# W51FXXXXS16_EVB_NONOFFICIAL_2026-06-30.net
KiCad netlist of a schematic drawn in EasyEDA Pro
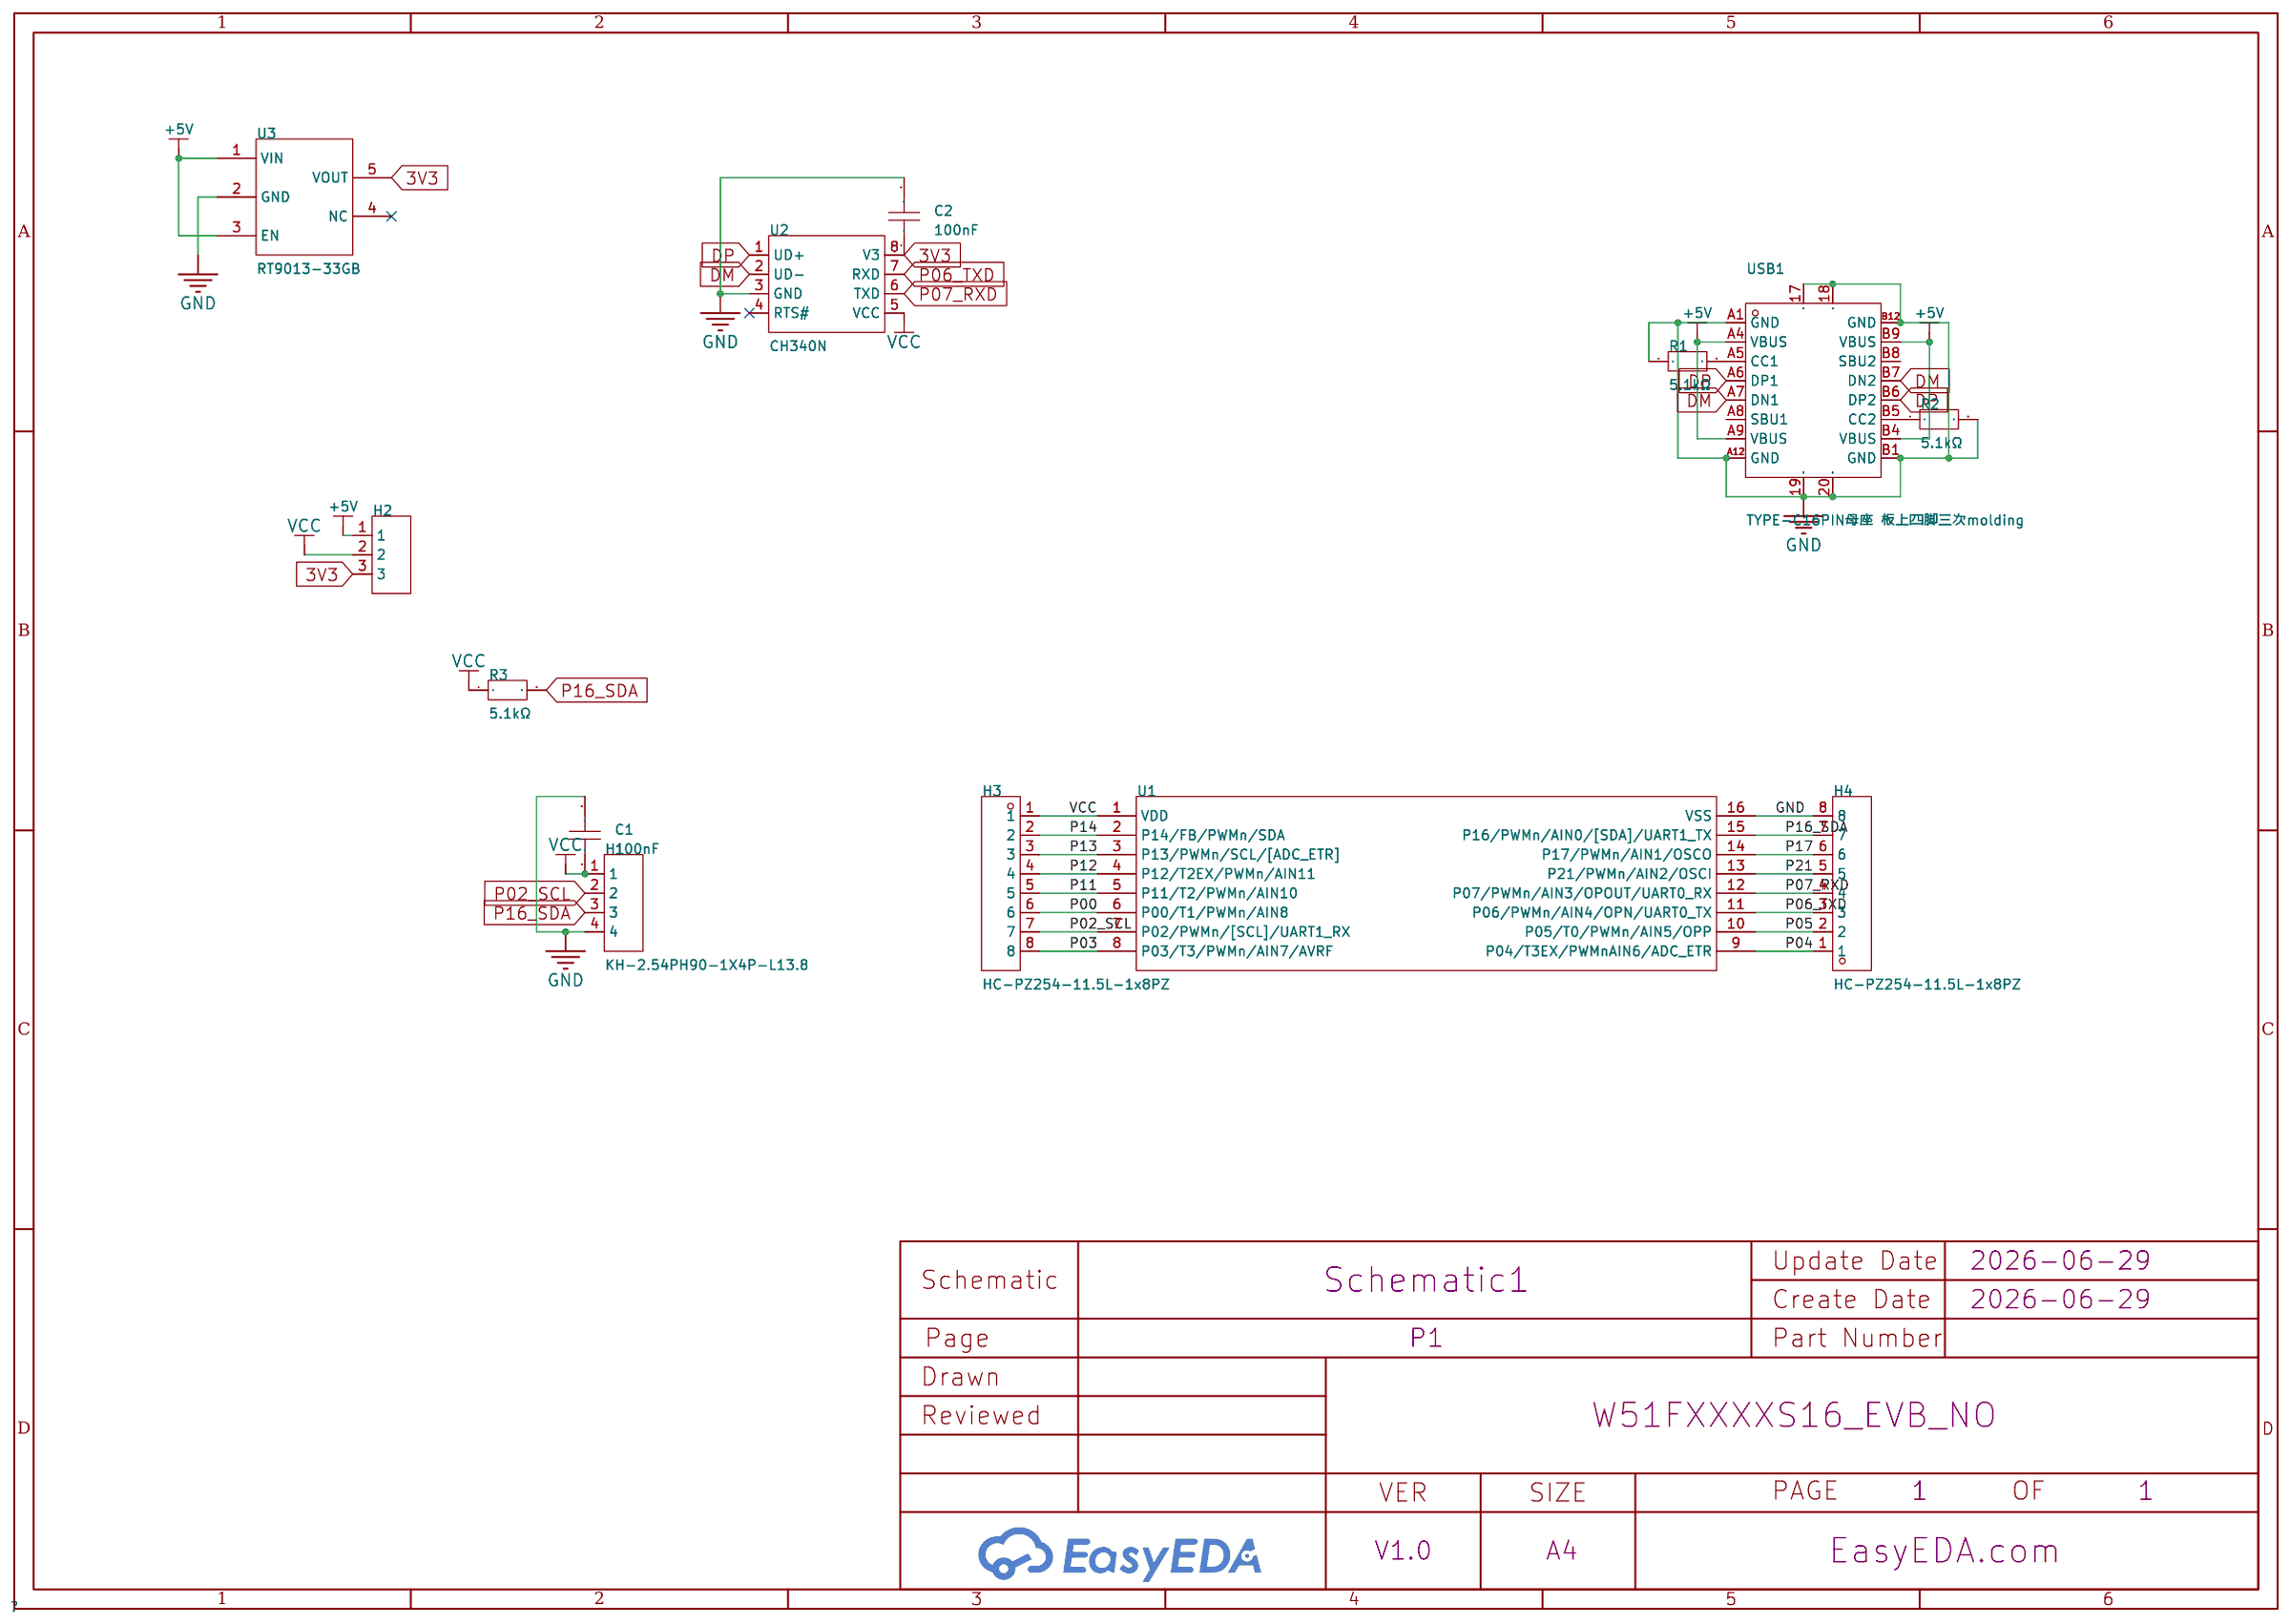
[diagram p0: schematic sheet]

(export (version "E")
  (design (tool "Eeschema 10.0.6"))
  (components
    (comp (ref "C1")
      (value "100nF")
      (footprint "easyedapro:C1206")
      (description "Capacitance:100nF Tolerance:±10% Tolerance:±10% Voltage Rating:200V Temperature Coefficient:X7R")
      (fields
        (field (name "Manufacturer Part") "VJ1206Y104KLCAJ32")
        (field (name "Manufacturer") "VISHAY(威世)")
      )
      (libsource (lib "easyedapro") (part "VJ1206Y104KLCAJ32"))
    )
    (comp (ref "C2")
      (value "100nF")
      (footprint "easyedapro:C1206")
      (description "Capacitance:100nF Tolerance:±10% Tolerance:±10% Voltage Rating:200V Temperature Coefficient:X7R")
      (fields
        (field (name "Manufacturer Part") "VJ1206Y104KLCAJ32")
        (field (name "Manufacturer") "VISHAY(威世)")
      )
      (libsource (lib "easyedapro") (part "VJ1206Y104KLCAJ32"))
    )
    (comp (ref "H1")
      (value "KH-2.54PH90-1X4P-L13.8")
      (footprint "easyedapro:HDR-TH_4P-P2.54-H-M-W10.4-N")
      (fields (field (name "Manufacturer") "kinghelm(金航标)"))
      (libsource (lib "easyedapro") (part "KH-2.54PH90-1X4P-L13.8"))
    )
    (comp (ref "H2")
      (value "~")
      (footprint "easyedapro:HDR-TH_3P-P2.54-V-M")
      (libsource (lib "easyedapro") (part "PZ254V-11-03P_C2937625"))
    )
    (comp (ref "H3")
      (value "HC-PZ254-11.5L-1x8PZ")
      (footprint "easyedapro:HDR-TH_8P-P2.54-V-M")
      (fields (field (name "Manufacturer") "HC(虹成电子)"))
      (libsource (lib "easyedapro") (part "HC-PZ254-11.5L-1X8PZ"))
    )
    (comp (ref "H4")
      (value "HC-PZ254-11.5L-1x8PZ")
      (footprint "easyedapro:HDR-TH_8P-P2.54-V-M")
      (fields (field (name "Manufacturer") "HC(虹成电子)"))
      (libsource (lib "easyedapro") (part "HC-PZ254-11.5L-1X8PZ"))
    )
    (comp (ref "R1")
      (value "5.1kΩ")
      (footprint "easyedapro:R1206")
      (fields
        (field (name "Manufacturer Part") "CQ06W4F5101T5E")
        (field (name "Manufacturer") "UNI-ROYAL(厚声)")
      )
      (libsource (lib "easyedapro") (part "CQ06W4F5101T5E"))
    )
    (comp (ref "R2")
      (value "5.1kΩ")
      (footprint "easyedapro:R1206")
      (fields
        (field (name "Manufacturer Part") "CQ06W4F5101T5E")
        (field (name "Manufacturer") "UNI-ROYAL(厚声)")
      )
      (libsource (lib "easyedapro") (part "CQ06W4F5101T5E"))
    )
    (comp (ref "R3")
      (value "5.1kΩ")
      (footprint "easyedapro:R1206")
      (fields
        (field (name "Manufacturer Part") "CQ06W4F5101T5E")
        (field (name "Manufacturer") "UNI-ROYAL(厚声)")
      )
      (libsource (lib "easyedapro") (part "CQ06W4F5101T5E"))
    )
    (comp (ref "U1")
      (value "~")
      (description "Low cost 1T 8051 MCU")
      (libsource (lib "easyedapro") (part "W51F6240S16"))
    )
    (comp (ref "U2")
      (value "CH340N")
      (footprint "easyedapro:SOP-8_L4.9-W3.9-P1.27-LS6.0-BL")
      (fields (field (name "Manufacturer") "WCH(南京沁恒)"))
      (libsource (lib "easyedapro") (part "CH340N_C2977777"))
    )
    (comp (ref "U3")
      (value "RT9013-33GB")
      (footprint "easyedapro:SOT-23-5_L3.0-W1.7-P0.95-LS2.8-BL")
      (fields (field (name "Manufacturer") "RICHTEK(立锜)"))
      (libsource (lib "easyedapro") (part "RT9013-33GB"))
    )
    (comp (ref "USB1")
      (value "TYPE-C16PIN母座 板上四脚三次molding")
      (footprint "easyedapro:USB-SMD_TYPE-C16PIN")
      (libsource (lib "easyedapro") (part "TYPE-C16PIN母座 板上四脚三次MOLDING"))
    )
  )
  (nets
    (net (code "1") (name "+5V") (class "Default")
      (node (ref "H2") (pin "1") (pinfunction "1_1") (pintype "unspecified"))
      (node (ref "U3") (pin "1") (pinfunction "VIN_1") (pintype "unspecified"))
      (node (ref "U3") (pin "3") (pinfunction "EN_3") (pintype "unspecified"))
      (node (ref "USB1") (pin "A4") (pinfunction "VBUS_A4") (pintype "input"))
      (node (ref "USB1") (pin "A9") (pinfunction "VBUS_A9") (pintype "input"))
      (node (ref "USB1") (pin "B4") (pinfunction "VBUS_B4") (pintype "input"))
      (node (ref "USB1") (pin "B9") (pinfunction "VBUS_B9") (pintype "input"))
    )
    (net (code "2") (name "/P00") (class "Default")
      (node (ref "H3") (pin "6") (pinfunction "6_6") (pintype "unspecified"))
      (node (ref "U1") (pin "6") (pinfunction "P00/T1/PWMn/AIN8_6") (pintype "input"))
    )
    (net (code "3") (name "/P03") (class "Default")
      (node (ref "H3") (pin "8") (pinfunction "8_8") (pintype "unspecified"))
      (node (ref "U1") (pin "8") (pinfunction "P03/T3/PWMn/AIN7/AVRF_8") (pintype "input"))
    )
    (net (code "4") (name "/P04") (class "Default")
      (node (ref "H4") (pin "1") (pinfunction "1_1") (pintype "unspecified"))
      (node (ref "U1") (pin "9") (pinfunction "P04/T3EX/PWMnAIN6/ADC_ETR_9") (pintype "input"))
    )
    (net (code "5") (name "/P05") (class "Default")
      (node (ref "H4") (pin "2") (pinfunction "2_2") (pintype "unspecified"))
      (node (ref "U1") (pin "10") (pinfunction "P05/T0/PWMn/AIN5/OPP_10") (pintype "input"))
    )
    (net (code "6") (name "/P11") (class "Default")
      (node (ref "H3") (pin "5") (pinfunction "5_5") (pintype "unspecified"))
      (node (ref "U1") (pin "5") (pinfunction "P11/T2/PWMn/AIN10_5") (pintype "input"))
    )
    (net (code "7") (name "/P12") (class "Default")
      (node (ref "H3") (pin "4") (pinfunction "4_4") (pintype "unspecified"))
      (node (ref "U1") (pin "4") (pinfunction "P12/T2EX/PWMn/AIN11_4") (pintype "input"))
    )
    (net (code "8") (name "/P13") (class "Default")
      (node (ref "H3") (pin "3") (pinfunction "3_3") (pintype "unspecified"))
      (node (ref "U1") (pin "3") (pinfunction "P13/PWMn/SCL/[ADC_ETR]_3") (pintype "input"))
    )
    (net (code "9") (name "/P14") (class "Default")
      (node (ref "H3") (pin "2") (pinfunction "2_2") (pintype "unspecified"))
      (node (ref "U1") (pin "2") (pinfunction "P14/FB/PWMn/SDA_2") (pintype "input"))
    )
    (net (code "10") (name "/P17") (class "Default")
      (node (ref "H4") (pin "6") (pinfunction "6_6") (pintype "unspecified"))
      (node (ref "U1") (pin "14") (pinfunction "P17/PWMn/AIN1/OSCO_14") (pintype "input"))
    )
    (net (code "11") (name "/P21") (class "Default")
      (node (ref "H4") (pin "5") (pinfunction "5_5") (pintype "unspecified"))
      (node (ref "U1") (pin "13") (pinfunction "P21/PWMn/AIN2/OSCI_13") (pintype "input"))
    )
    (net (code "12") (name "3V3") (class "Default")
      (node (ref "C2") (pin "1") (pinfunction "1_1") (pintype "unspecified"))
      (node (ref "H2") (pin "3") (pinfunction "3_3") (pintype "unspecified"))
      (node (ref "U2") (pin "8") (pinfunction "V3_8") (pintype "unspecified"))
      (node (ref "U3") (pin "5") (pinfunction "VOUT_5") (pintype "unspecified"))
    )
    (net (code "13") (name "DM") (class "Default")
      (node (ref "U2") (pin "2") (pinfunction "UD-_2") (pintype "unspecified"))
      (node (ref "USB1") (pin "A7") (pinfunction "DN1_A7") (pintype "input"))
      (node (ref "USB1") (pin "B7") (pinfunction "DN2_B7") (pintype "input"))
    )
    (net (code "14") (name "DP") (class "Default")
      (node (ref "U2") (pin "1") (pinfunction "UD+_1") (pintype "unspecified"))
      (node (ref "USB1") (pin "A6") (pinfunction "DP1_A6") (pintype "input"))
      (node (ref "USB1") (pin "B6") (pinfunction "DP2_B6") (pintype "input"))
    )
    (net (code "15") (name "GND") (class "Default")
      (node (ref "C1") (pin "2") (pinfunction "2_2") (pintype "unspecified"))
      (node (ref "C2") (pin "2") (pinfunction "2_2") (pintype "unspecified"))
      (node (ref "H1") (pin "4") (pinfunction "4_4") (pintype "unspecified"))
      (node (ref "H4") (pin "8") (pinfunction "8_8") (pintype "unspecified"))
      (node (ref "R1") (pin "1") (pinfunction "1_1") (pintype "unspecified"))
      (node (ref "R2") (pin "2") (pinfunction "2_2") (pintype "unspecified"))
      (node (ref "U1") (pin "16") (pinfunction "VSS_16") (pintype "input"))
      (node (ref "U2") (pin "3") (pinfunction "GND_3") (pintype "unspecified"))
      (node (ref "U3") (pin "2") (pinfunction "GND_2") (pintype "unspecified"))
      (node (ref "USB1") (pin "17") (pinfunction "17_17") (pintype "input"))
      (node (ref "USB1") (pin "18") (pinfunction "18_18") (pintype "input"))
      (node (ref "USB1") (pin "19") (pinfunction "19_19") (pintype "input"))
      (node (ref "USB1") (pin "20") (pinfunction "20_20") (pintype "input"))
      (node (ref "USB1") (pin "A1") (pinfunction "GND_A1") (pintype "input"))
      (node (ref "USB1") (pin "A12") (pinfunction "GND_A12") (pintype "input"))
      (node (ref "USB1") (pin "B1") (pinfunction "GND_B1") (pintype "input"))
      (node (ref "USB1") (pin "B12") (pinfunction "GND_B12") (pintype "input"))
    )
    (net (code "16") (name "Net-(USB1-CC1)") (class "Default")
      (node (ref "R1") (pin "2") (pinfunction "2_2") (pintype "unspecified"))
      (node (ref "USB1") (pin "A5") (pinfunction "CC1_A5") (pintype "input"))
    )
    (net (code "17") (name "Net-(USB1-CC2)") (class "Default")
      (node (ref "R2") (pin "1") (pinfunction "1_1") (pintype "unspecified"))
      (node (ref "USB1") (pin "B5") (pinfunction "CC2_B5") (pintype "input"))
    )
    (net (code "18") (name "P02_SCL") (class "Default")
      (node (ref "H1") (pin "2") (pinfunction "2_2") (pintype "unspecified"))
      (node (ref "H3") (pin "7") (pinfunction "7_7") (pintype "unspecified"))
      (node (ref "U1") (pin "7") (pinfunction "P02/PWMn/[SCL]/UART1_RX_7") (pintype "input"))
    )
    (net (code "19") (name "P06_TXD") (class "Default")
      (node (ref "H4") (pin "3") (pinfunction "3_3") (pintype "unspecified"))
      (node (ref "U1") (pin "11") (pinfunction "P06/PWMn/AIN4/OPN/UART0_TX_11") (pintype "input"))
      (node (ref "U2") (pin "7") (pinfunction "RXD_7") (pintype "unspecified"))
    )
    (net (code "20") (name "P07_RXD") (class "Default")
      (node (ref "H4") (pin "4") (pinfunction "4_4") (pintype "unspecified"))
      (node (ref "U1") (pin "12") (pinfunction "P07/PWMn/AIN3/OPOUT/UART0_RX_12") (pintype "input"))
      (node (ref "U2") (pin "6") (pinfunction "TXD_6") (pintype "unspecified"))
    )
    (net (code "21") (name "P16_SDA") (class "Default")
      (node (ref "H1") (pin "3") (pinfunction "3_3") (pintype "unspecified"))
      (node (ref "H4") (pin "7") (pinfunction "7_7") (pintype "unspecified"))
      (node (ref "R3") (pin "2") (pinfunction "2_2") (pintype "unspecified"))
      (node (ref "U1") (pin "15") (pinfunction "P16/PWMn/AIN0/[SDA]/UART1_TX_15") (pintype "input"))
    )
    (net (code "22") (name "VCC") (class "Default")
      (node (ref "C1") (pin "1") (pinfunction "1_1") (pintype "unspecified"))
      (node (ref "H1") (pin "1") (pinfunction "1_1") (pintype "unspecified"))
      (node (ref "H2") (pin "2") (pinfunction "2_2") (pintype "unspecified"))
      (node (ref "H3") (pin "1") (pinfunction "1_1") (pintype "unspecified"))
      (node (ref "R3") (pin "1") (pinfunction "1_1") (pintype "unspecified"))
      (node (ref "U1") (pin "1") (pinfunction "VDD_1") (pintype "input"))
      (node (ref "U2") (pin "5") (pinfunction "VCC_5") (pintype "unspecified"))
    )
    (net (code "23") (name "unconnected-(U2-RTS#-Pad4)") (class "Default")
      (node (ref "U2") (pin "4") (pinfunction "RTS#_4") (pintype "unspecified+no_connect"))
    )
    (net (code "24") (name "unconnected-(U3-NC-Pad4)") (class "Default")
      (node (ref "U3") (pin "4") (pinfunction "NC_4") (pintype "unspecified+no_connect"))
    )
    (net (code "25") (name "unconnected-(USB1-SBU1-PadA8)") (class "Default")
      (node (ref "USB1") (pin "A8") (pinfunction "SBU1_A8") (pintype "input"))
    )
    (net (code "26") (name "unconnected-(USB1-SBU2-PadB8)") (class "Default")
      (node (ref "USB1") (pin "B8") (pinfunction "SBU2_B8") (pintype "input"))
    )
  )
)
